# ETH.net
KiCad netlist of a schematic drawn in Altium Designer
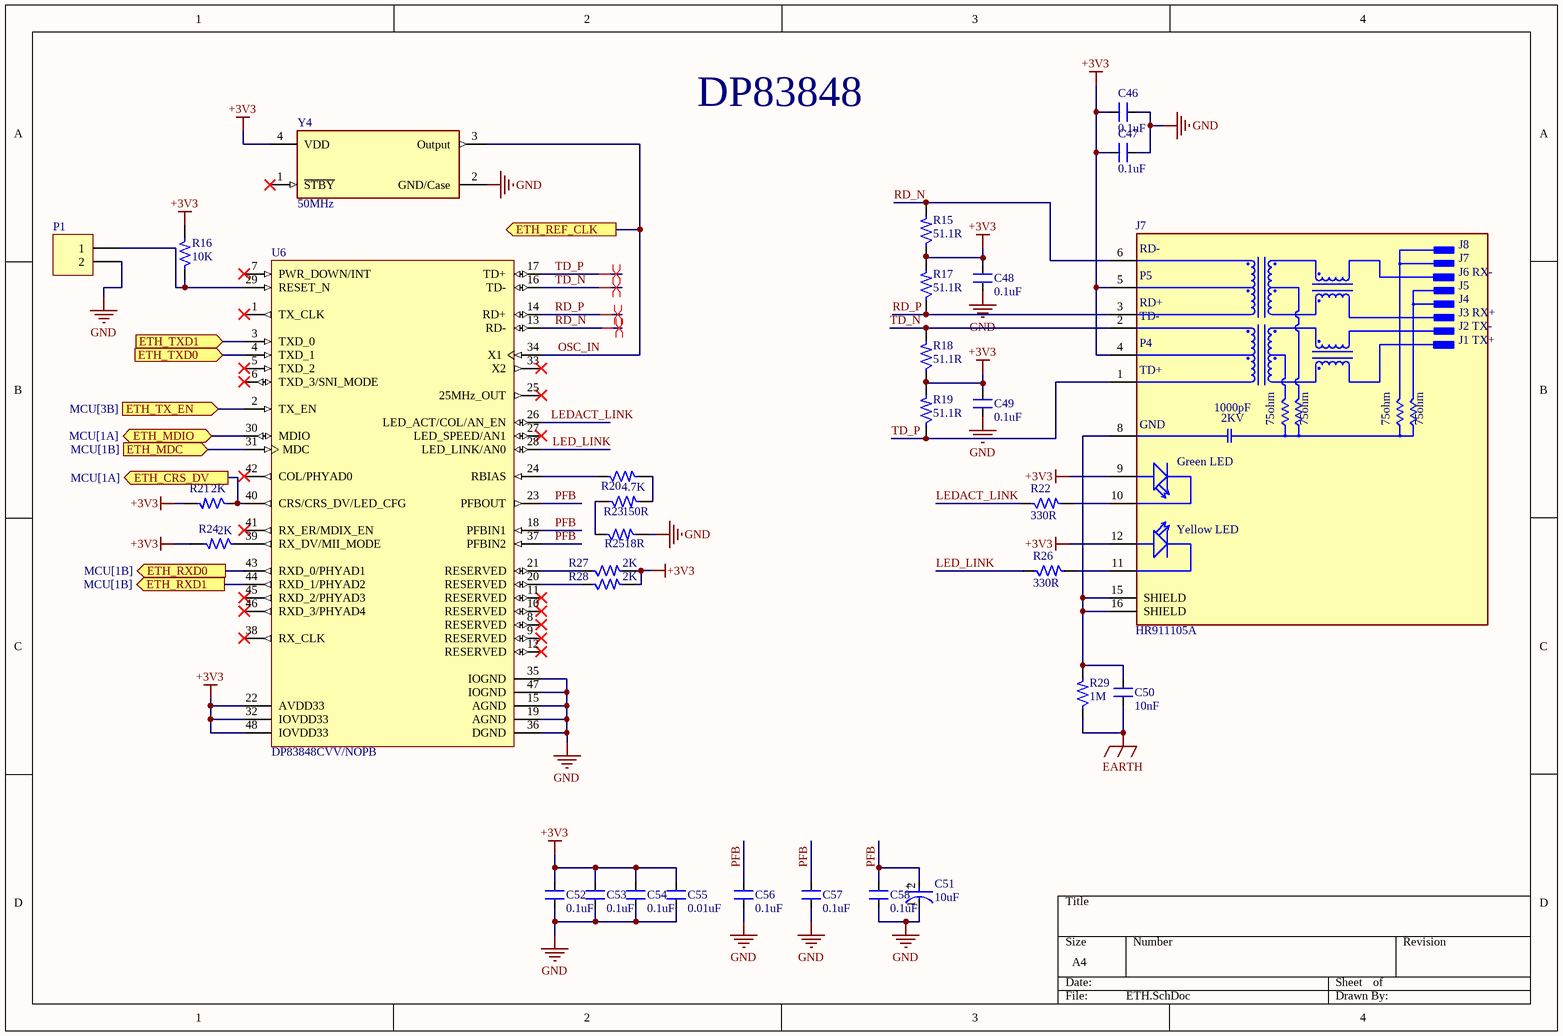
[diagram p0: ETH.SchDoc]

(export (version "E")
  (design (tool "Eeschema 10.0.6"))
  (components
    (comp (ref "C46")
      (value "0.1uF")
      (footprint "CAP_0805")
      (description "0.1µF ±20% 50V Ceramic Capacitor X7R 0805 (2012 Metric)")
      (fields
        (field (name "MANUFACTURER") "Samsung Electro-Mechanics")
        (field (name "MANUFACTURER PART NUMBER") "CL21B104MBCNNNC")
      )
      (libsource (lib "ESTEEMPCBLIB") (part "CAP_0.1uF-50V-20%-0805"))
    )
    (comp (ref "C47")
      (value "0.1uF")
      (footprint "CAP_0805")
      (description "0.1µF ±20% 50V Ceramic Capacitor X7R 0805 (2012 Metric)")
      (fields
        (field (name "MANUFACTURER") "Samsung Electro-Mechanics")
        (field (name "MANUFACTURER PART NUMBER") "CL21B104MBCNNNC")
      )
      (libsource (lib "ESTEEMPCBLIB") (part "CAP_0.1uF-50V-20%-0805"))
    )
    (comp (ref "C48")
      (value "0.1uF")
      (footprint "CAP_0805")
      (description "0.1µF ±20% 50V Ceramic Capacitor X7R 0805 (2012 Metric)")
      (fields
        (field (name "MANUFACTURER") "Samsung Electro-Mechanics")
        (field (name "MANUFACTURER PART NUMBER") "CL21B104MBCNNNC")
      )
      (libsource (lib "ESTEEMPCBLIB") (part "CAP_0.1uF-50V-20%-0805"))
    )
    (comp (ref "C49")
      (value "0.1uF")
      (footprint "CAP_0805")
      (description "0.1µF ±20% 50V Ceramic Capacitor X7R 0805 (2012 Metric)")
      (fields
        (field (name "MANUFACTURER") "Samsung Electro-Mechanics")
        (field (name "MANUFACTURER PART NUMBER") "CL21B104MBCNNNC")
      )
      (libsource (lib "ESTEEMPCBLIB") (part "CAP_0.1uF-50V-20%-0805"))
    )
    (comp (ref "C50")
      (value "10nF")
      (footprint "CAP_P196_102X287_H332_RAD_TH")
      (description "10000pF ±10% 1000V (1kV) Ceramic Capacitor X7R Radial")
      (fields
        (field (name "MANUFACTURER") "Yageo")
        (field (name "MANUFACTURER PART NUMBER") "RDER73A103K2K1H03B")
      )
      (libsource (lib "ESTEEMPCBLIB") (part "CAP_10nF-1KV-10%-RAD-TH"))
    )
    (comp (ref "C51")
      (value "10uF")
      (footprint "FP-293DA-MFG")
      (fields (field (name "TOLERANCE") "20%"))
      (libsource (lib "Altium Content Vault") (part "a00bbbee19879c290e62620ae7e47b1"))
    )
    (comp (ref "C52")
      (value "0.1uF")
      (footprint "CAP_0805")
      (description "0.1µF ±20% 50V Ceramic Capacitor X7R 0805 (2012 Metric)")
      (fields
        (field (name "MANUFACTURER") "Samsung Electro-Mechanics")
        (field (name "MANUFACTURER PART NUMBER") "CL21B104MBCNNNC")
      )
      (libsource (lib "ESTEEMPCBLIB") (part "CAP_0.1uF-50V-20%-0805"))
    )
    (comp (ref "C53")
      (value "0.1uF")
      (footprint "CAP_0805")
      (description "0.1µF ±20% 50V Ceramic Capacitor X7R 0805 (2012 Metric)")
      (fields
        (field (name "MANUFACTURER") "Samsung Electro-Mechanics")
        (field (name "MANUFACTURER PART NUMBER") "CL21B104MBCNNNC")
      )
      (libsource (lib "ESTEEMPCBLIB") (part "CAP_0.1uF-50V-20%-0805"))
    )
    (comp (ref "C54")
      (value "0.1uF")
      (footprint "CAP_0805")
      (description "0.1µF ±20% 50V Ceramic Capacitor X7R 0805 (2012 Metric)")
      (fields
        (field (name "MANUFACTURER") "Samsung Electro-Mechanics")
        (field (name "MANUFACTURER PART NUMBER") "CL21B104MBCNNNC")
      )
      (libsource (lib "ESTEEMPCBLIB") (part "CAP_0.1uF-50V-20%-0805"))
    )
    (comp (ref "C55")
      (value "0.01uF")
      (footprint "CAP_0805")
      (description "0.1µF ±20% 50V Ceramic Capacitor X7R 0805 (2012 Metric)")
      (fields
        (field (name "MANUFACTURER") "Samsung Electro-Mechanics")
        (field (name "MANUFACTURER PART NUMBER") "CL21B104MBCNNNC")
      )
      (libsource (lib "ESTEEMPCBLIB") (part "CAP_0.1uF-50V-20%-0805"))
    )
    (comp (ref "C56")
      (value "0.1uF")
      (footprint "CAP_0805")
      (description "0.1µF ±20% 50V Ceramic Capacitor X7R 0805 (2012 Metric)")
      (fields
        (field (name "MANUFACTURER") "Samsung Electro-Mechanics")
        (field (name "MANUFACTURER PART NUMBER") "CL21B104MBCNNNC")
      )
      (libsource (lib "ESTEEMPCBLIB") (part "CAP_0.1uF-50V-20%-0805"))
    )
    (comp (ref "C57")
      (value "0.1uF")
      (footprint "CAP_0805")
      (description "0.1µF ±20% 50V Ceramic Capacitor X7R 0805 (2012 Metric)")
      (fields
        (field (name "MANUFACTURER") "Samsung Electro-Mechanics")
        (field (name "MANUFACTURER PART NUMBER") "CL21B104MBCNNNC")
      )
      (libsource (lib "ESTEEMPCBLIB") (part "CAP_0.1uF-50V-20%-0805"))
    )
    (comp (ref "C58")
      (value "0.1uF")
      (footprint "CAP_0805")
      (description "0.1µF ±20% 50V Ceramic Capacitor X7R 0805 (2012 Metric)")
      (fields
        (field (name "MANUFACTURER") "Samsung Electro-Mechanics")
        (field (name "MANUFACTURER PART NUMBER") "CL21B104MBCNNNC")
      )
      (libsource (lib "ESTEEMPCBLIB") (part "CAP_0.1uF-50V-20%-0805"))
    )
    (comp (ref "J7")
      (value "HR911105A")
      (footprint "HANRUN_HR911105A")
      (description "DIP RJ45 Connector;")
      (fields (field (name "MF") "hanrun"))
      (libsource (lib "Persional LIB") (part "HR911105A"))
    )
    (comp (ref "P1")
      (value "BERSTICK 2.5MM, MALE")
      (footprint "CON2_100_43D62_TH_ST")
      (description "2 Pins, 1 Row 2.54mm Pitch, Straight bergstrip, Male")
      (fields (field (name "MANUFACTURER PART NUMBER") "NA") (field (name "MANUFACTURER") "Samtec"))
      (libsource (lib "ESTEEMPCBLIB") (part "CON-BS-PLG_2X1-100-ST-TH"))
    )
    (comp (ref "R15")
      (value "51.1R")
      (footprint "RES_0603")
      (description "51.1 Ohms ±1% 0.1W, 1/10W Chip Resistor 0603 (1608 Metric) Thick Film")
      (fields
        (field (name "MANUFACTURER") "Vishay Dale")
        (field (name "MANUFACTURER PART NUMBER") "CRCW060351R1FKEAC")
      )
      (libsource (lib "ESTEEMPCBLIB") (part "RES_51.1R-0.1W-1%-0603"))
    )
    (comp (ref "R16")
      (value "10K")
      (footprint "RES_0805")
      (description "10 kOhms ±1% 0.125W, 1/8W Chip Resistor 0805 (2012 Metric) Automotive AEC-Q200 Thick Film")
      (fields (field (name "MANUFACTURER") "CTS") (field (name "MANUFACTURER PART NUMBER") "WR08X1002FTL"))
      (libsource (lib "ESTEEMPCBLIB") (part "RES_10K-0.125W-1%-0805"))
    )
    (comp (ref "R17")
      (value "51.1R")
      (footprint "RES_0603")
      (description "51.1 Ohms ±1% 0.1W, 1/10W Chip Resistor 0603 (1608 Metric) Thick Film")
      (fields
        (field (name "MANUFACTURER") "Vishay Dale")
        (field (name "MANUFACTURER PART NUMBER") "CRCW060351R1FKEAC")
      )
      (libsource (lib "ESTEEMPCBLIB") (part "RES_51.1R-0.1W-1%-0603"))
    )
    (comp (ref "R18")
      (value "51.1R")
      (footprint "RES_0603")
      (description "51.1 Ohms ±1% 0.1W, 1/10W Chip Resistor 0603 (1608 Metric) Thick Film")
      (fields
        (field (name "MANUFACTURER") "Vishay Dale")
        (field (name "MANUFACTURER PART NUMBER") "CRCW060351R1FKEAC")
      )
      (libsource (lib "ESTEEMPCBLIB") (part "RES_51.1R-0.1W-1%-0603"))
    )
    (comp (ref "R19")
      (value "51.1R")
      (footprint "RES_0603")
      (description "51.1 Ohms ±1% 0.1W, 1/10W Chip Resistor 0603 (1608 Metric) Thick Film")
      (fields
        (field (name "MANUFACTURER") "Vishay Dale")
        (field (name "MANUFACTURER PART NUMBER") "CRCW060351R1FKEAC")
      )
      (libsource (lib "ESTEEMPCBLIB") (part "RES_51.1R-0.1W-1%-0603"))
    )
    (comp (ref "R20")
      (value "4.7K")
      (footprint "RES_0805")
      (description "4.7 kOhms ±1% 0.125W, 1/8W Chip Resistor 0805 (2012 Metric) Moisture Resistant Thick Film")
      (fields
        (field (name "MANUFACTURER") "TE Connectivity")
        (field (name "MANUFACTURER PART NUMBER") "RC0805FR-074K7L")
      )
      (libsource (lib "ESTEEMPCBLIB") (part "RES_4.7K-0.125W-1%-0805"))
    )
    (comp (ref "R21")
      (value "2K")
      (footprint "RES_0805")
      (description "2 kOhms ±1% 0.125W, 1/8W Chip Resistor 0805 (2012 Metric) Moisture Resistant Thick Film")
      (fields
        (field (name "MANUFACTURER") "TE Connectivity")
        (field (name "MANUFACTURER PART NUMBER") "RC0805FR-072KL")
      )
      (libsource (lib "ESTEEMPCBLIB") (part "RES_2K-0.125W-1%-0805"))
    )
    (comp (ref "R22")
      (value "330R")
      (footprint "RES_0805")
      (description "330 Ohms ±1% 0.125W, 1/8W Chip Resistor 0805 (2012 Metric) Automotive AEC-Q200 Thick Film")
      (fields (field (name "MANUFACTURER") "Walsin") (field (name "MANUFACTURER PART NUMBER") "WR08X3300FTL"))
      (libsource (lib "ESTEEMPCBLIB") (part "RES_330R-0.125W-1%-0805"))
    )
    (comp (ref "R23")
      (value "150R")
      (footprint "RES_0805")
      (description "150 Ohms ±1% 0.125W, 1/8W Chip Resistor 0805 (2012 Metric) Automotive AEC-Q200 Thick Film")
      (fields (field (name "MANUFACTURER") "Walsin") (field (name "MANUFACTURER PART NUMBER") "WR08X1500FTL"))
      (libsource (lib "ESTEEMPCBLIB") (part "RES_150R-0.125W-1%-0805"))
    )
    (comp (ref "R24")
      (value "2K")
      (footprint "RES_0805")
      (description "2 kOhms ±1% 0.125W, 1/8W Chip Resistor 0805 (2012 Metric) Moisture Resistant Thick Film")
      (fields
        (field (name "MANUFACTURER") "TE Connectivity")
        (field (name "MANUFACTURER PART NUMBER") "RC0805FR-072KL")
      )
      (libsource (lib "ESTEEMPCBLIB") (part "RES_2K-0.125W-1%-0805"))
    )
    (comp (ref "R25")
      (value "18R")
      (footprint "RES_0805")
      (description "18.7 kOhms ±1% 0.125W, 1/8W Chip Resistor 0805 (2012 Metric) Automotive AEC-Q200 Thick Film")
      (fields
        (field (name "MANUFACTURER") "Yageo")
        (field (name "MANUFACTURER PART NUMBER") "RMCF0805FT18K7")
      )
      (libsource (lib "ESTEEMPCBLIB") (part "RES_18.7K-0.125W-1%-0805"))
    )
    (comp (ref "R26")
      (value "330R")
      (footprint "RES_0805")
      (description "330 Ohms ±1% 0.125W, 1/8W Chip Resistor 0805 (2012 Metric) Automotive AEC-Q200 Thick Film")
      (fields (field (name "MANUFACTURER") "Walsin") (field (name "MANUFACTURER PART NUMBER") "WR08X3300FTL"))
      (libsource (lib "ESTEEMPCBLIB") (part "RES_330R-0.125W-1%-0805"))
    )
    (comp (ref "R27")
      (value "2K")
      (footprint "RES_0805")
      (description "2 kOhms ±1% 0.125W, 1/8W Chip Resistor 0805 (2012 Metric) Moisture Resistant Thick Film")
      (fields
        (field (name "MANUFACTURER") "TE Connectivity")
        (field (name "MANUFACTURER PART NUMBER") "RC0805FR-072KL")
      )
      (libsource (lib "ESTEEMPCBLIB") (part "RES_2K-0.125W-1%-0805"))
    )
    (comp (ref "R28")
      (value "2K")
      (footprint "RES_0805")
      (description "2 kOhms ±1% 0.125W, 1/8W Chip Resistor 0805 (2012 Metric) Moisture Resistant Thick Film")
      (fields
        (field (name "MANUFACTURER") "TE Connectivity")
        (field (name "MANUFACTURER PART NUMBER") "RC0805FR-072KL")
      )
      (libsource (lib "ESTEEMPCBLIB") (part "RES_2K-0.125W-1%-0805"))
    )
    (comp (ref "R29")
      (value "1M")
      (footprint "RES_1206")
      (fields (field (name "MANUFACTURER") "Walsin") (field (name "MANUFACTURER PART NUMBER") "WR12X1004FTL"))
      (libsource (lib "ESTEEMPCBLIB") (part "RES_1M-0.25W-1%-1206"))
    )
    (comp (ref "U6")
      (value "DP83848CVV/NOPB")
      (footprint "PT0048A_M")
      (fields (field (name "MANUFACTURER") "Texas Instruments"))
      (libsource (lib "Altium Content Vault") (part "IN-LNTX-DP83848CVV"))
    )
    (comp (ref "Y4")
      (value "50MHz")
      (footprint "FP-ASE-MFG")
      (description "XTAL Oscillator 50MHz ±25ppm CMOS 3.3V 4-SMD 3.2mm x 2.5mm")
      (libsource (lib "Altium Content Vault") (part "61a724e6190563596ac712fef61ad37"))
    )
  )
  (nets
    (net (code "1") (name "+3V3") (class "Default")
      (node (ref "C46") (pin "1") (pinfunction "1_1") (pintype "passive"))
      (node (ref "C47") (pin "1") (pinfunction "1_1") (pintype "passive"))
      (node (ref "C48") (pin "2") (pinfunction "2_2") (pintype "passive"))
      (node (ref "C49") (pin "2") (pinfunction "2_2") (pintype "passive"))
      (node (ref "C52") (pin "1") (pinfunction "1_1") (pintype "passive"))
      (node (ref "C53") (pin "1") (pinfunction "1_1") (pintype "passive"))
      (node (ref "C54") (pin "2") (pinfunction "2_2") (pintype "passive"))
      (node (ref "C55") (pin "2") (pinfunction "2_2") (pintype "passive"))
      (node (ref "J7") (pin "12") (pinfunction "YA_12") (pintype "passive"))
      (node (ref "J7") (pin "4") (pinfunction "P4_4") (pintype "passive"))
      (node (ref "J7") (pin "5") (pinfunction "P5_5") (pintype "passive"))
      (node (ref "J7") (pin "9") (pinfunction "GA_9") (pintype "passive"))
      (node (ref "R15") (pin "1") (pinfunction "1_1") (pintype "passive"))
      (node (ref "R16") (pin "2") (pinfunction "2_2") (pintype "passive"))
      (node (ref "R17") (pin "2") (pinfunction "2_2") (pintype "passive"))
      (node (ref "R18") (pin "1") (pinfunction "1_1") (pintype "passive"))
      (node (ref "R19") (pin "2") (pinfunction "2_2") (pintype "passive"))
      (node (ref "R21") (pin "2") (pinfunction "2_2") (pintype "passive"))
      (node (ref "R24") (pin "2") (pinfunction "2_2") (pintype "passive"))
      (node (ref "R27") (pin "2") (pinfunction "2_2") (pintype "passive"))
      (node (ref "R28") (pin "2") (pinfunction "2_2") (pintype "passive"))
      (node (ref "U6") (pin "22") (pinfunction "AVDD33_22") (pintype "power_in"))
      (node (ref "U6") (pin "32") (pinfunction "IOVDD33_32") (pintype "power_in"))
      (node (ref "U6") (pin "48") (pinfunction "IOVDD33_48") (pintype "power_in"))
      (node (ref "Y4") (pin "4") (pinfunction "VDD_4") (pintype "power_in"))
    )
    (net (code "2") (name "/ETH_CRS_DV") (class "Default")
      (node (ref "R21") (pin "1") (pinfunction "1_1") (pintype "passive"))
      (node (ref "U6") (pin "40") (pinfunction "CRS/CRS_DV/LED_CFG_40") (pintype "output"))
    )
    (net (code "3") (name "/ETH_MDC") (class "Default")
      (node (ref "U6") (pin "31") (pinfunction "MDC_31") (pintype "input"))
    )
    (net (code "4") (name "/ETH_MDIO") (class "Default")
      (node (ref "U6") (pin "30") (pinfunction "MDIO_30") (pintype "bidirectional"))
    )
    (net (code "5") (name "/ETH_RXD0") (class "Default")
      (node (ref "U6") (pin "43") (pinfunction "RXD_0/PHYAD1_43") (pintype "output"))
    )
    (net (code "6") (name "/ETH_RXD1") (class "Default")
      (node (ref "U6") (pin "44") (pinfunction "RXD_1/PHYAD2_44") (pintype "output"))
    )
    (net (code "7") (name "/ETH_TXD0") (class "Default")
      (node (ref "U6") (pin "4") (pinfunction "TXD_1_4") (pintype "input"))
    )
    (net (code "8") (name "/ETH_TXD1") (class "Default")
      (node (ref "U6") (pin "3") (pinfunction "TXD_0_3") (pintype "input"))
    )
    (net (code "9") (name "/ETH_TX_EN") (class "Default")
      (node (ref "U6") (pin "2") (pinfunction "TX_EN_2") (pintype "input"))
    )
    (net (code "10") (name "/LEDACT_LINK") (class "Default")
      (node (ref "R22") (pin "1") (pinfunction "1_1") (pintype "passive"))
      (node (ref "U6") (pin "26") (pinfunction "LED_ACT/COL/AN_EN_26") (pintype "bidirectional"))
    )
    (net (code "11") (name "/LED_LINK") (class "Default")
      (node (ref "R26") (pin "1") (pinfunction "1_1") (pintype "passive"))
      (node (ref "U6") (pin "28") (pinfunction "LED_LINK/AN0_28") (pintype "bidirectional"))
    )
    (net (code "12") (name "/OSC_IN") (class "Default")
      (node (ref "U6") (pin "34") (pinfunction "X1_34") (pintype "input"))
      (node (ref "Y4") (pin "3") (pinfunction "Output_3") (pintype "output"))
    )
    (net (code "13") (name "/PFB") (class "Default")
      (node (ref "C51") (pin "2") (pinfunction "A_2") (pintype "passive"))
      (node (ref "C56") (pin "1") (pinfunction "1_1") (pintype "passive"))
      (node (ref "C57") (pin "1") (pinfunction "1_1") (pintype "passive"))
      (node (ref "C58") (pin "2") (pinfunction "2_2") (pintype "passive"))
      (node (ref "U6") (pin "18") (pinfunction "PFBIN1_18") (pintype "input"))
      (node (ref "U6") (pin "23") (pinfunction "PFBOUT_23") (pintype "output"))
      (node (ref "U6") (pin "37") (pinfunction "PFBIN2_37") (pintype "input"))
    )
    (net (code "14") (name "/RD_N") (class "Default")
      (node (ref "J7") (pin "6") (pinfunction "RD-_6") (pintype "passive"))
      (node (ref "R15") (pin "2") (pinfunction "2_2") (pintype "passive"))
      (node (ref "U6") (pin "13") (pinfunction "RD-_13") (pintype "bidirectional"))
    )
    (net (code "15") (name "/RD_P") (class "Default")
      (node (ref "J7") (pin "3") (pinfunction "RD+_3") (pintype "passive"))
      (node (ref "R17") (pin "1") (pinfunction "1_1") (pintype "passive"))
      (node (ref "U6") (pin "14") (pinfunction "RD+_14") (pintype "bidirectional"))
    )
    (net (code "16") (name "/TD_N") (class "Default")
      (node (ref "J7") (pin "2") (pinfunction "TD-_2") (pintype "passive"))
      (node (ref "R18") (pin "2") (pinfunction "2_2") (pintype "passive"))
      (node (ref "U6") (pin "16") (pinfunction "TD-_16") (pintype "bidirectional"))
    )
    (net (code "17") (name "/TD_P") (class "Default")
      (node (ref "J7") (pin "1") (pinfunction "TD+_1") (pintype "passive"))
      (node (ref "R19") (pin "1") (pinfunction "1_1") (pintype "passive"))
      (node (ref "U6") (pin "17") (pinfunction "TD+_17") (pintype "bidirectional"))
    )
    (net (code "18") (name "EARTH") (class "Default")
      (node (ref "C50") (pin "1") (pinfunction "1_1") (pintype "passive"))
      (node (ref "R29") (pin "1") (pinfunction "1_1") (pintype "passive"))
    )
    (net (code "19") (name "GND") (class "Default")
      (node (ref "C46") (pin "2") (pinfunction "2_2") (pintype "passive"))
      (node (ref "C47") (pin "2") (pinfunction "2_2") (pintype "passive"))
      (node (ref "C48") (pin "1") (pinfunction "1_1") (pintype "passive"))
      (node (ref "C49") (pin "1") (pinfunction "1_1") (pintype "passive"))
      (node (ref "C51") (pin "1") (pinfunction "C_1") (pintype "passive"))
      (node (ref "C52") (pin "2") (pinfunction "2_2") (pintype "passive"))
      (node (ref "C53") (pin "2") (pinfunction "2_2") (pintype "passive"))
      (node (ref "C54") (pin "1") (pinfunction "1_1") (pintype "passive"))
      (node (ref "C55") (pin "1") (pinfunction "1_1") (pintype "passive"))
      (node (ref "C56") (pin "2") (pinfunction "2_2") (pintype "passive"))
      (node (ref "C57") (pin "2") (pinfunction "2_2") (pintype "passive"))
      (node (ref "C58") (pin "1") (pinfunction "1_1") (pintype "passive"))
      (node (ref "P1") (pin "2") (pinfunction "2_2") (pintype "passive"))
      (node (ref "R25") (pin "2") (pinfunction "2_2") (pintype "passive"))
      (node (ref "U6") (pin "15") (pinfunction "AGND_15") (pintype "passive"))
      (node (ref "U6") (pin "19") (pinfunction "AGND_19") (pintype "passive"))
      (node (ref "U6") (pin "35") (pinfunction "IOGND_35") (pintype "passive"))
      (node (ref "U6") (pin "36") (pinfunction "DGND_36") (pintype "passive"))
      (node (ref "U6") (pin "47") (pinfunction "IOGND_47") (pintype "passive"))
      (node (ref "Y4") (pin "2") (pinfunction "GND/Case_2") (pintype "power_in"))
    )
    (net (code "20") (name "Net-(J7-GC)") (class "Default")
      (node (ref "J7") (pin "10") (pinfunction "GC_10") (pintype "passive"))
      (node (ref "R22") (pin "2") (pinfunction "2_2") (pintype "passive"))
    )
    (net (code "21") (name "Net-(J7-GND)") (class "Default")
      (node (ref "C50") (pin "2") (pinfunction "2_2") (pintype "passive"))
      (node (ref "J7") (pin "15") (pinfunction "SHIELD_15") (pintype "passive"))
      (node (ref "J7") (pin "16") (pinfunction "SHIELD_16") (pintype "passive"))
      (node (ref "J7") (pin "8") (pinfunction "GND_8") (pintype "power_in"))
      (node (ref "R29") (pin "2") (pinfunction "2_2") (pintype "passive"))
    )
    (net (code "22") (name "Net-(J7-YC)") (class "Default")
      (node (ref "J7") (pin "11") (pinfunction "YC_11") (pintype "passive"))
      (node (ref "R26") (pin "2") (pinfunction "2_2") (pintype "passive"))
    )
    (net (code "23") (name "Net-(R20-Pad2)") (class "Default")
      (node (ref "R20") (pin "2") (pinfunction "2_2") (pintype "passive"))
      (node (ref "R23") (pin "2") (pinfunction "2_2") (pintype "passive"))
    )
    (net (code "24") (name "Net-(R23-Pad1)") (class "Default")
      (node (ref "R23") (pin "1") (pinfunction "1_1") (pintype "passive"))
      (node (ref "R25") (pin "1") (pinfunction "1_1") (pintype "passive"))
    )
    (net (code "25") (name "Net-(R27-Pad1)") (class "Default")
      (node (ref "R27") (pin "1") (pinfunction "1_1") (pintype "passive"))
      (node (ref "U6") (pin "21") (pinfunction "RESERVED_21") (pintype "bidirectional"))
    )
    (net (code "26") (name "Net-(R28-Pad1)") (class "Default")
      (node (ref "R28") (pin "1") (pinfunction "1_1") (pintype "passive"))
      (node (ref "U6") (pin "20") (pinfunction "RESERVED_20") (pintype "bidirectional"))
    )
    (net (code "27") (name "Net-(U6-RBIAS)") (class "Default")
      (node (ref "R20") (pin "1") (pinfunction "1_1") (pintype "passive"))
      (node (ref "U6") (pin "24") (pinfunction "RBIAS_24") (pintype "input"))
    )
    (net (code "28") (name "Net-(U6-RESET_N)") (class "Default")
      (node (ref "P1") (pin "1") (pinfunction "1_1") (pintype "passive"))
      (node (ref "R16") (pin "1") (pinfunction "1_1") (pintype "passive"))
      (node (ref "U6") (pin "29") (pinfunction "RESET_N_29") (pintype "input"))
    )
    (net (code "29") (name "Net-(U6-RX_DV{slash}MII_MODE)") (class "Default")
      (node (ref "R24") (pin "1") (pinfunction "1_1") (pintype "passive"))
      (node (ref "U6") (pin "39") (pinfunction "RX_DV/MII_MODE_39") (pintype "output"))
    )
    (net (code "30") (name "unconnected-(U6-25MHz_OUT-Pad25)") (class "Default")
      (node (ref "U6") (pin "25") (pinfunction "25MHz_OUT_25") (pintype "output+no_connect"))
    )
    (net (code "31") (name "unconnected-(U6-COL{slash}PHYAD0-Pad42)") (class "Default")
      (node (ref "U6") (pin "42") (pinfunction "COL/PHYAD0_42") (pintype "output+no_connect"))
    )
    (net (code "32") (name "unconnected-(U6-LED_SPEED{slash}AN1-Pad27)") (class "Default")
      (node (ref "U6") (pin "27") (pinfunction "LED_SPEED/AN1_27") (pintype "bidirectional+no_connect"))
    )
    (net (code "33") (name "unconnected-(U6-PWR_DOWN{slash}INT-Pad7)") (class "Default")
      (node (ref "U6") (pin "7") (pinfunction "PWR_DOWN/INT_7") (pintype "input+no_connect"))
    )
    (net (code "34") (name "unconnected-(U6-RESERVED-Pad8)") (class "Default")
      (node (ref "U6") (pin "8") (pinfunction "RESERVED_8") (pintype "bidirectional+no_connect"))
    )
    (net (code "35") (name "unconnected-(U6-RESERVED-Pad9)") (class "Default")
      (node (ref "U6") (pin "9") (pinfunction "RESERVED_9") (pintype "bidirectional+no_connect"))
    )
    (net (code "36") (name "unconnected-(U6-RESERVED-Pad10)") (class "Default")
      (node (ref "U6") (pin "10") (pinfunction "RESERVED_10") (pintype "bidirectional+no_connect"))
    )
    (net (code "37") (name "unconnected-(U6-RESERVED-Pad11)") (class "Default")
      (node (ref "U6") (pin "11") (pinfunction "RESERVED_11") (pintype "bidirectional+no_connect"))
    )
    (net (code "38") (name "unconnected-(U6-RESERVED-Pad12)") (class "Default")
      (node (ref "U6") (pin "12") (pinfunction "RESERVED_12") (pintype "bidirectional+no_connect"))
    )
    (net (code "39") (name "unconnected-(U6-RXD_2{slash}PHYAD3-Pad45)") (class "Default")
      (node (ref "U6") (pin "45") (pinfunction "RXD_2/PHYAD3_45") (pintype "output+no_connect"))
    )
    (net (code "40") (name "unconnected-(U6-RXD_3{slash}PHYAD4-Pad46)") (class "Default")
      (node (ref "U6") (pin "46") (pinfunction "RXD_3/PHYAD4_46") (pintype "output+no_connect"))
    )
    (net (code "41") (name "unconnected-(U6-RX_CLK-Pad38)") (class "Default")
      (node (ref "U6") (pin "38") (pinfunction "RX_CLK_38") (pintype "output+no_connect"))
    )
    (net (code "42") (name "unconnected-(U6-RX_ER{slash}MDIX_EN-Pad41)") (class "Default")
      (node (ref "U6") (pin "41") (pinfunction "RX_ER/MDIX_EN_41") (pintype "output+no_connect"))
    )
    (net (code "43") (name "unconnected-(U6-TXD_2-Pad5)") (class "Default")
      (node (ref "U6") (pin "5") (pinfunction "TXD_2_5") (pintype "input+no_connect"))
    )
    (net (code "44") (name "unconnected-(U6-TXD_3{slash}SNI_MODE-Pad6)") (class "Default")
      (node (ref "U6") (pin "6") (pinfunction "TXD_3/SNI_MODE_6") (pintype "bidirectional+no_connect"))
    )
    (net (code "45") (name "unconnected-(U6-TX_CLK-Pad1)") (class "Default")
      (node (ref "U6") (pin "1") (pinfunction "TX_CLK_1") (pintype "output+no_connect"))
    )
    (net (code "46") (name "unconnected-(U6-X2-Pad33)") (class "Default")
      (node (ref "U6") (pin "33") (pinfunction "X2_33") (pintype "output+no_connect"))
    )
    (net (code "47") (name "unconnected-(Y4-~{STBY}-Pad1)") (class "Default")
      (node (ref "Y4") (pin "1") (pinfunction "~{STBY}_1") (pintype "input+no_connect"))
    )
  )
)
